# ADC088S022.net
KiCad netlist of a schematic drawn in Altium Designer
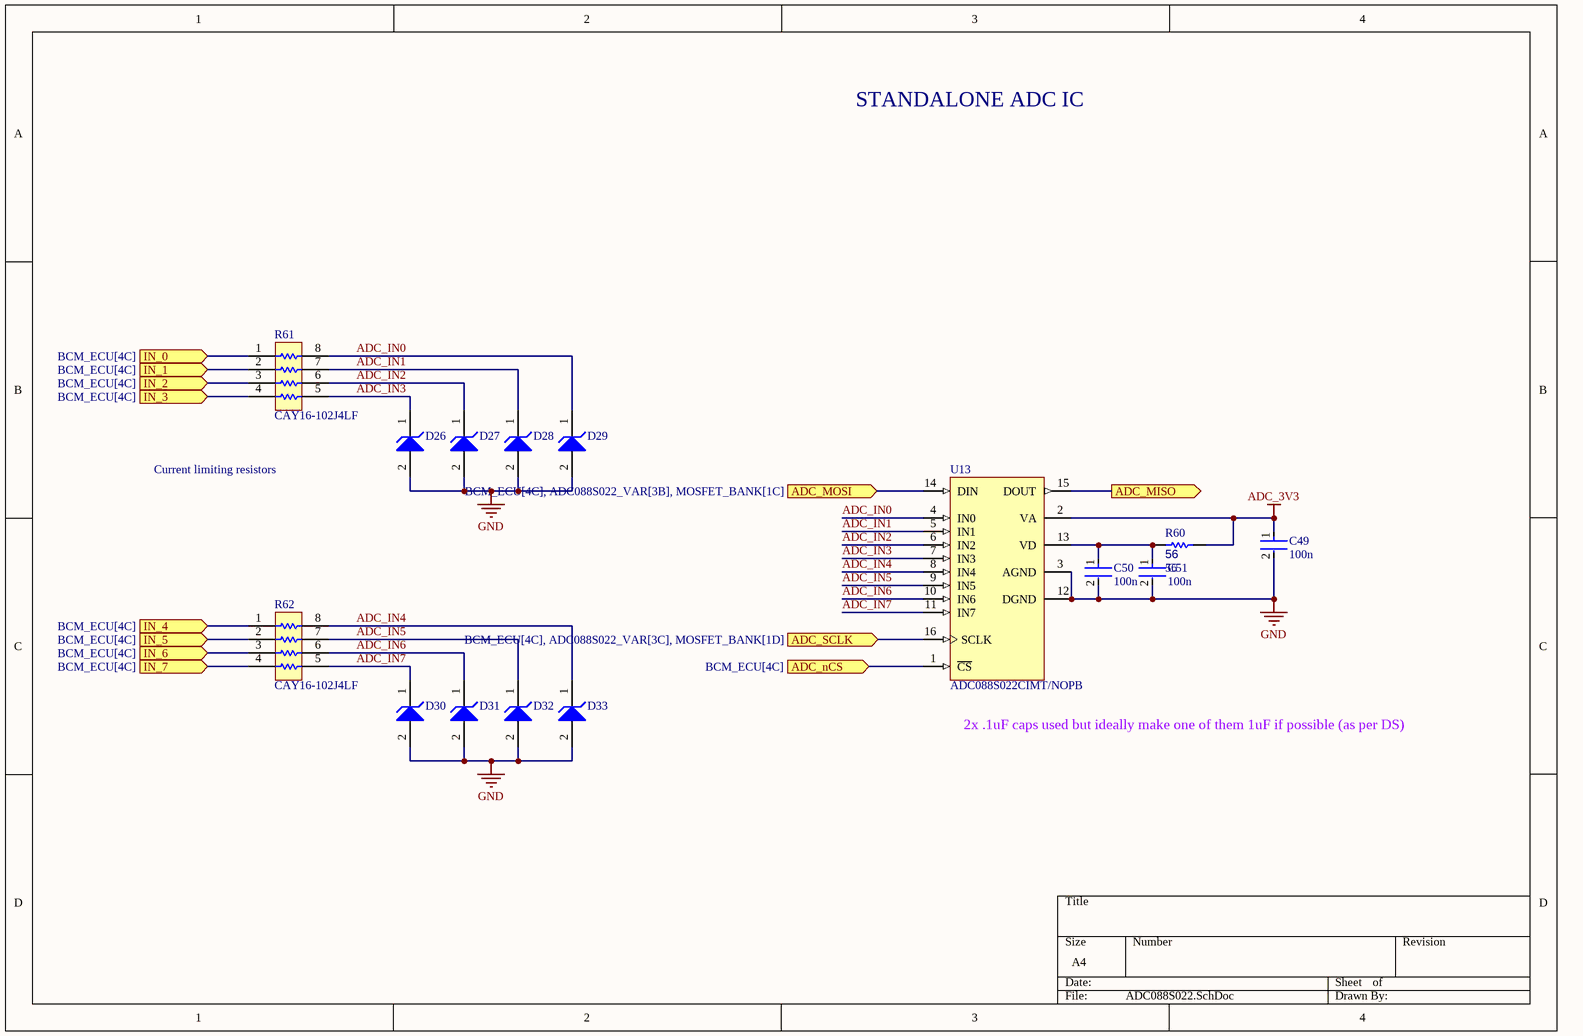
[diagram p0: ADC088S022.SchDoc]

(export (version "E")
  (design (tool "Eeschema 10.0.6"))
  (components
    (comp (ref "C49")
      (value "100n")
      (footprint "FP-0402-L_1_0_0_05-W_0_5-IPC_A")
      (description "LARGE PADS, 0402 CAP, CHANGE COMMENT TO MATCH REAL P/N")
      (libsource (lib "Space Concordia") (part "b4654b650e69147ec39a6b967a45e02"))
    )
    (comp (ref "C50")
      (value "100n")
      (footprint "FP-0402-L_1_0_0_05-W_0_5-IPC_A")
      (description "LARGE PADS, 0402 CAP, CHANGE COMMENT TO MATCH REAL P/N")
      (libsource (lib "Space Concordia") (part "b4654b650e69147ec39a6b967a45e02"))
    )
    (comp (ref "C51")
      (value "100n")
      (footprint "FP-0402-L_1_0_0_05-W_0_5-IPC_A")
      (description "LARGE PADS, 0402 CAP, CHANGE COMMENT TO MATCH REAL P/N")
      (libsource (lib "Space Concordia") (part "b4654b650e69147ec39a6b967a45e02"))
    )
    (comp (ref "D26")
      (value "MM5Z3V3T1G")
      (footprint "ONSC-SOD-523-2-502-01_V")
      (description "Zener Voltage Regulator, 500 mW, 2-Pin SOD-523, Pb-Free, Tape and Reel")
      (fields (field (name "MANUFACTURER") "On Semiconductor"))
      (libsource (lib "Altium Content Vault") (part "ONSC-K1A2-2"))
    )
    (comp (ref "D27")
      (value "MM5Z3V3T1G")
      (footprint "ONSC-SOD-523-2-502-01_V")
      (description "Zener Voltage Regulator, 500 mW, 2-Pin SOD-523, Pb-Free, Tape and Reel")
      (fields (field (name "MANUFACTURER") "On Semiconductor"))
      (libsource (lib "Altium Content Vault") (part "ONSC-K1A2-2"))
    )
    (comp (ref "D28")
      (value "MM5Z3V3T1G")
      (footprint "ONSC-SOD-523-2-502-01_V")
      (description "Zener Voltage Regulator, 500 mW, 2-Pin SOD-523, Pb-Free, Tape and Reel")
      (fields (field (name "MANUFACTURER") "On Semiconductor"))
      (libsource (lib "Altium Content Vault") (part "ONSC-K1A2-2"))
    )
    (comp (ref "D29")
      (value "MM5Z3V3T1G")
      (footprint "ONSC-SOD-523-2-502-01_V")
      (description "Zener Voltage Regulator, 500 mW, 2-Pin SOD-523, Pb-Free, Tape and Reel")
      (fields (field (name "MANUFACTURER") "On Semiconductor"))
      (libsource (lib "Altium Content Vault") (part "ONSC-K1A2-2"))
    )
    (comp (ref "D30")
      (value "MM5Z3V3T1G")
      (footprint "ONSC-SOD-523-2-502-01_V")
      (description "Zener Voltage Regulator, 500 mW, 2-Pin SOD-523, Pb-Free, Tape and Reel")
      (fields (field (name "MANUFACTURER") "On Semiconductor"))
      (libsource (lib "Altium Content Vault") (part "ONSC-K1A2-2"))
    )
    (comp (ref "D31")
      (value "MM5Z3V3T1G")
      (footprint "ONSC-SOD-523-2-502-01_V")
      (description "Zener Voltage Regulator, 500 mW, 2-Pin SOD-523, Pb-Free, Tape and Reel")
      (fields (field (name "MANUFACTURER") "On Semiconductor"))
      (libsource (lib "Altium Content Vault") (part "ONSC-K1A2-2"))
    )
    (comp (ref "D32")
      (value "MM5Z3V3T1G")
      (footprint "ONSC-SOD-523-2-502-01_V")
      (description "Zener Voltage Regulator, 500 mW, 2-Pin SOD-523, Pb-Free, Tape and Reel")
      (fields (field (name "MANUFACTURER") "On Semiconductor"))
      (libsource (lib "Altium Content Vault") (part "ONSC-K1A2-2"))
    )
    (comp (ref "D33")
      (value "MM5Z3V3T1G")
      (footprint "ONSC-SOD-523-2-502-01_V")
      (description "Zener Voltage Regulator, 500 mW, 2-Pin SOD-523, Pb-Free, Tape and Reel")
      (fields (field (name "MANUFACTURER") "On Semiconductor"))
      (libsource (lib "Altium Content Vault") (part "ONSC-K1A2-2"))
    )
    (comp (ref "R60")
      (value "56")
      (footprint "R0603B")
      (description "Resistor")
      (fields (field (name "ALTIUM_VALUE") "56"))
      (libsource (lib "Space Concordia") (part "Resistor"))
    )
    (comp (ref "R61")
      (value "CAY16-102J4LF")
      (footprint "BOUR-CAY16-J4_V")
      (description "Chip Resistor Array, 1 KOhm, +/- 5%, 62.5 mW, -55 to 125 degC, 8-Pin SMD, RoHS, Tape and Reel")
      (fields (field (name "TOLERANCE") "1%"))
      (libsource (lib "Altium Content Vault") (part "RES-P-8"))
    )
    (comp (ref "R62")
      (value "CAY16-102J4LF")
      (footprint "BOUR-CAY16-J4_V")
      (description "Chip Resistor Array, 1 KOhm, +/- 5%, 62.5 mW, -55 to 125 degC, 8-Pin SMD, RoHS, Tape and Reel")
      (fields (field (name "TOLERANCE") "1%"))
      (libsource (lib "Altium Content Vault") (part "RES-P-8"))
    )
    (comp (ref "U13")
      (value "ADC088S022CIMT/NOPB")
      (footprint "MTC16_L")
      (description "8-Channel, 50 kSPS to 200 kSPS, 8-Bit A/D Converter, 16-pin TSSOP, Pb-Free")
      (fields (field (name "MANUFACTURER") "National Semiconductor"))
      (libsource (lib "Altium Content Vault") (part "CON-ADC-ADC108S052CIMT"))
    )
  )
  (nets
    (net (code "1") (name "/ADC_IN0") (class "Default")
      (node (ref "D29") (pin "1") (pinfunction "K_1") (pintype "passive"))
      (node (ref "R61") (pin "8") (pinfunction "8_8") (pintype "passive"))
      (node (ref "U13") (pin "4") (pinfunction "IN0_4") (pintype "input"))
    )
    (net (code "2") (name "/ADC_IN1") (class "Default")
      (node (ref "D28") (pin "1") (pinfunction "K_1") (pintype "passive"))
      (node (ref "R61") (pin "7") (pinfunction "7_7") (pintype "passive"))
      (node (ref "U13") (pin "5") (pinfunction "IN1_5") (pintype "input"))
    )
    (net (code "3") (name "/ADC_IN2") (class "Default")
      (node (ref "D27") (pin "1") (pinfunction "K_1") (pintype "passive"))
      (node (ref "R61") (pin "6") (pinfunction "6_6") (pintype "passive"))
      (node (ref "U13") (pin "6") (pinfunction "IN2_6") (pintype "input"))
    )
    (net (code "4") (name "/ADC_IN3") (class "Default")
      (node (ref "D26") (pin "1") (pinfunction "K_1") (pintype "passive"))
      (node (ref "R61") (pin "5") (pinfunction "5_5") (pintype "passive"))
      (node (ref "U13") (pin "7") (pinfunction "IN3_7") (pintype "input"))
    )
    (net (code "5") (name "/ADC_IN4") (class "Default")
      (node (ref "D33") (pin "1") (pinfunction "K_1") (pintype "passive"))
      (node (ref "R62") (pin "8") (pinfunction "8_8") (pintype "passive"))
      (node (ref "U13") (pin "8") (pinfunction "IN4_8") (pintype "input"))
    )
    (net (code "6") (name "/ADC_IN5") (class "Default")
      (node (ref "D32") (pin "1") (pinfunction "K_1") (pintype "passive"))
      (node (ref "R62") (pin "7") (pinfunction "7_7") (pintype "passive"))
      (node (ref "U13") (pin "9") (pinfunction "IN5_9") (pintype "input"))
    )
    (net (code "7") (name "/ADC_IN6") (class "Default")
      (node (ref "D31") (pin "1") (pinfunction "K_1") (pintype "passive"))
      (node (ref "R62") (pin "6") (pinfunction "6_6") (pintype "passive"))
      (node (ref "U13") (pin "10") (pinfunction "IN6_10") (pintype "input"))
    )
    (net (code "8") (name "/ADC_IN7") (class "Default")
      (node (ref "D30") (pin "1") (pinfunction "K_1") (pintype "passive"))
      (node (ref "R62") (pin "5") (pinfunction "5_5") (pintype "passive"))
      (node (ref "U13") (pin "11") (pinfunction "IN7_11") (pintype "input"))
    )
    (net (code "9") (name "/ADC_MISO") (class "Default")
      (node (ref "U13") (pin "15") (pinfunction "DOUT_15") (pintype "output"))
    )
    (net (code "10") (name "/ADC_MOSI") (class "Default")
      (node (ref "U13") (pin "14") (pinfunction "DIN_14") (pintype "input"))
    )
    (net (code "11") (name "/ADC_SCLK") (class "Default")
      (node (ref "U13") (pin "16") (pinfunction "SCLK_16") (pintype "input"))
    )
    (net (code "12") (name "/ADC_nCS") (class "Default")
      (node (ref "U13") (pin "1") (pinfunction "~{CS}_1") (pintype "input"))
    )
    (net (code "13") (name "/IN_0") (class "Default")
      (node (ref "R61") (pin "1") (pinfunction "1_1") (pintype "passive"))
    )
    (net (code "14") (name "/IN_1") (class "Default")
      (node (ref "R61") (pin "2") (pinfunction "2_2") (pintype "passive"))
    )
    (net (code "15") (name "/IN_2") (class "Default")
      (node (ref "R61") (pin "3") (pinfunction "3_3") (pintype "passive"))
    )
    (net (code "16") (name "/IN_3") (class "Default")
      (node (ref "R61") (pin "4") (pinfunction "4_4") (pintype "passive"))
    )
    (net (code "17") (name "/IN_4") (class "Default")
      (node (ref "R62") (pin "1") (pinfunction "1_1") (pintype "passive"))
    )
    (net (code "18") (name "/IN_5") (class "Default")
      (node (ref "R62") (pin "2") (pinfunction "2_2") (pintype "passive"))
    )
    (net (code "19") (name "/IN_6") (class "Default")
      (node (ref "R62") (pin "3") (pinfunction "3_3") (pintype "passive"))
    )
    (net (code "20") (name "/IN_7") (class "Default")
      (node (ref "R62") (pin "4") (pinfunction "4_4") (pintype "passive"))
    )
    (net (code "21") (name "ADC_3V3") (class "Default")
      (node (ref "C49") (pin "1") (pinfunction "1_1") (pintype "passive"))
      (node (ref "R60") (pin "1") (pinfunction "1_1") (pintype "passive"))
      (node (ref "U13") (pin "2") (pinfunction "VA_2") (pintype "power_in"))
    )
    (net (code "22") (name "GND") (class "Default")
      (node (ref "C49") (pin "2") (pinfunction "2_2") (pintype "passive"))
      (node (ref "C50") (pin "2") (pinfunction "2_2") (pintype "passive"))
      (node (ref "C51") (pin "2") (pinfunction "2_2") (pintype "passive"))
      (node (ref "D26") (pin "2") (pinfunction "A_2") (pintype "passive"))
      (node (ref "D27") (pin "2") (pinfunction "A_2") (pintype "passive"))
      (node (ref "D28") (pin "2") (pinfunction "A_2") (pintype "passive"))
      (node (ref "D29") (pin "2") (pinfunction "A_2") (pintype "passive"))
      (node (ref "D30") (pin "2") (pinfunction "A_2") (pintype "passive"))
      (node (ref "D31") (pin "2") (pinfunction "A_2") (pintype "passive"))
      (node (ref "D32") (pin "2") (pinfunction "A_2") (pintype "passive"))
      (node (ref "D33") (pin "2") (pinfunction "A_2") (pintype "passive"))
      (node (ref "U13") (pin "12") (pinfunction "DGND_12") (pintype "power_in"))
      (node (ref "U13") (pin "3") (pinfunction "AGND_3") (pintype "power_in"))
    )
    (net (code "23") (name "Net-(U13-VD)") (class "Default")
      (node (ref "C50") (pin "1") (pinfunction "1_1") (pintype "passive"))
      (node (ref "C51") (pin "1") (pinfunction "1_1") (pintype "passive"))
      (node (ref "R60") (pin "2") (pinfunction "2_2") (pintype "passive"))
      (node (ref "U13") (pin "13") (pinfunction "VD_13") (pintype "power_in"))
    )
  )
)
